# Schematic.net
KiCad netlist of a schematic drawn in EAGLE
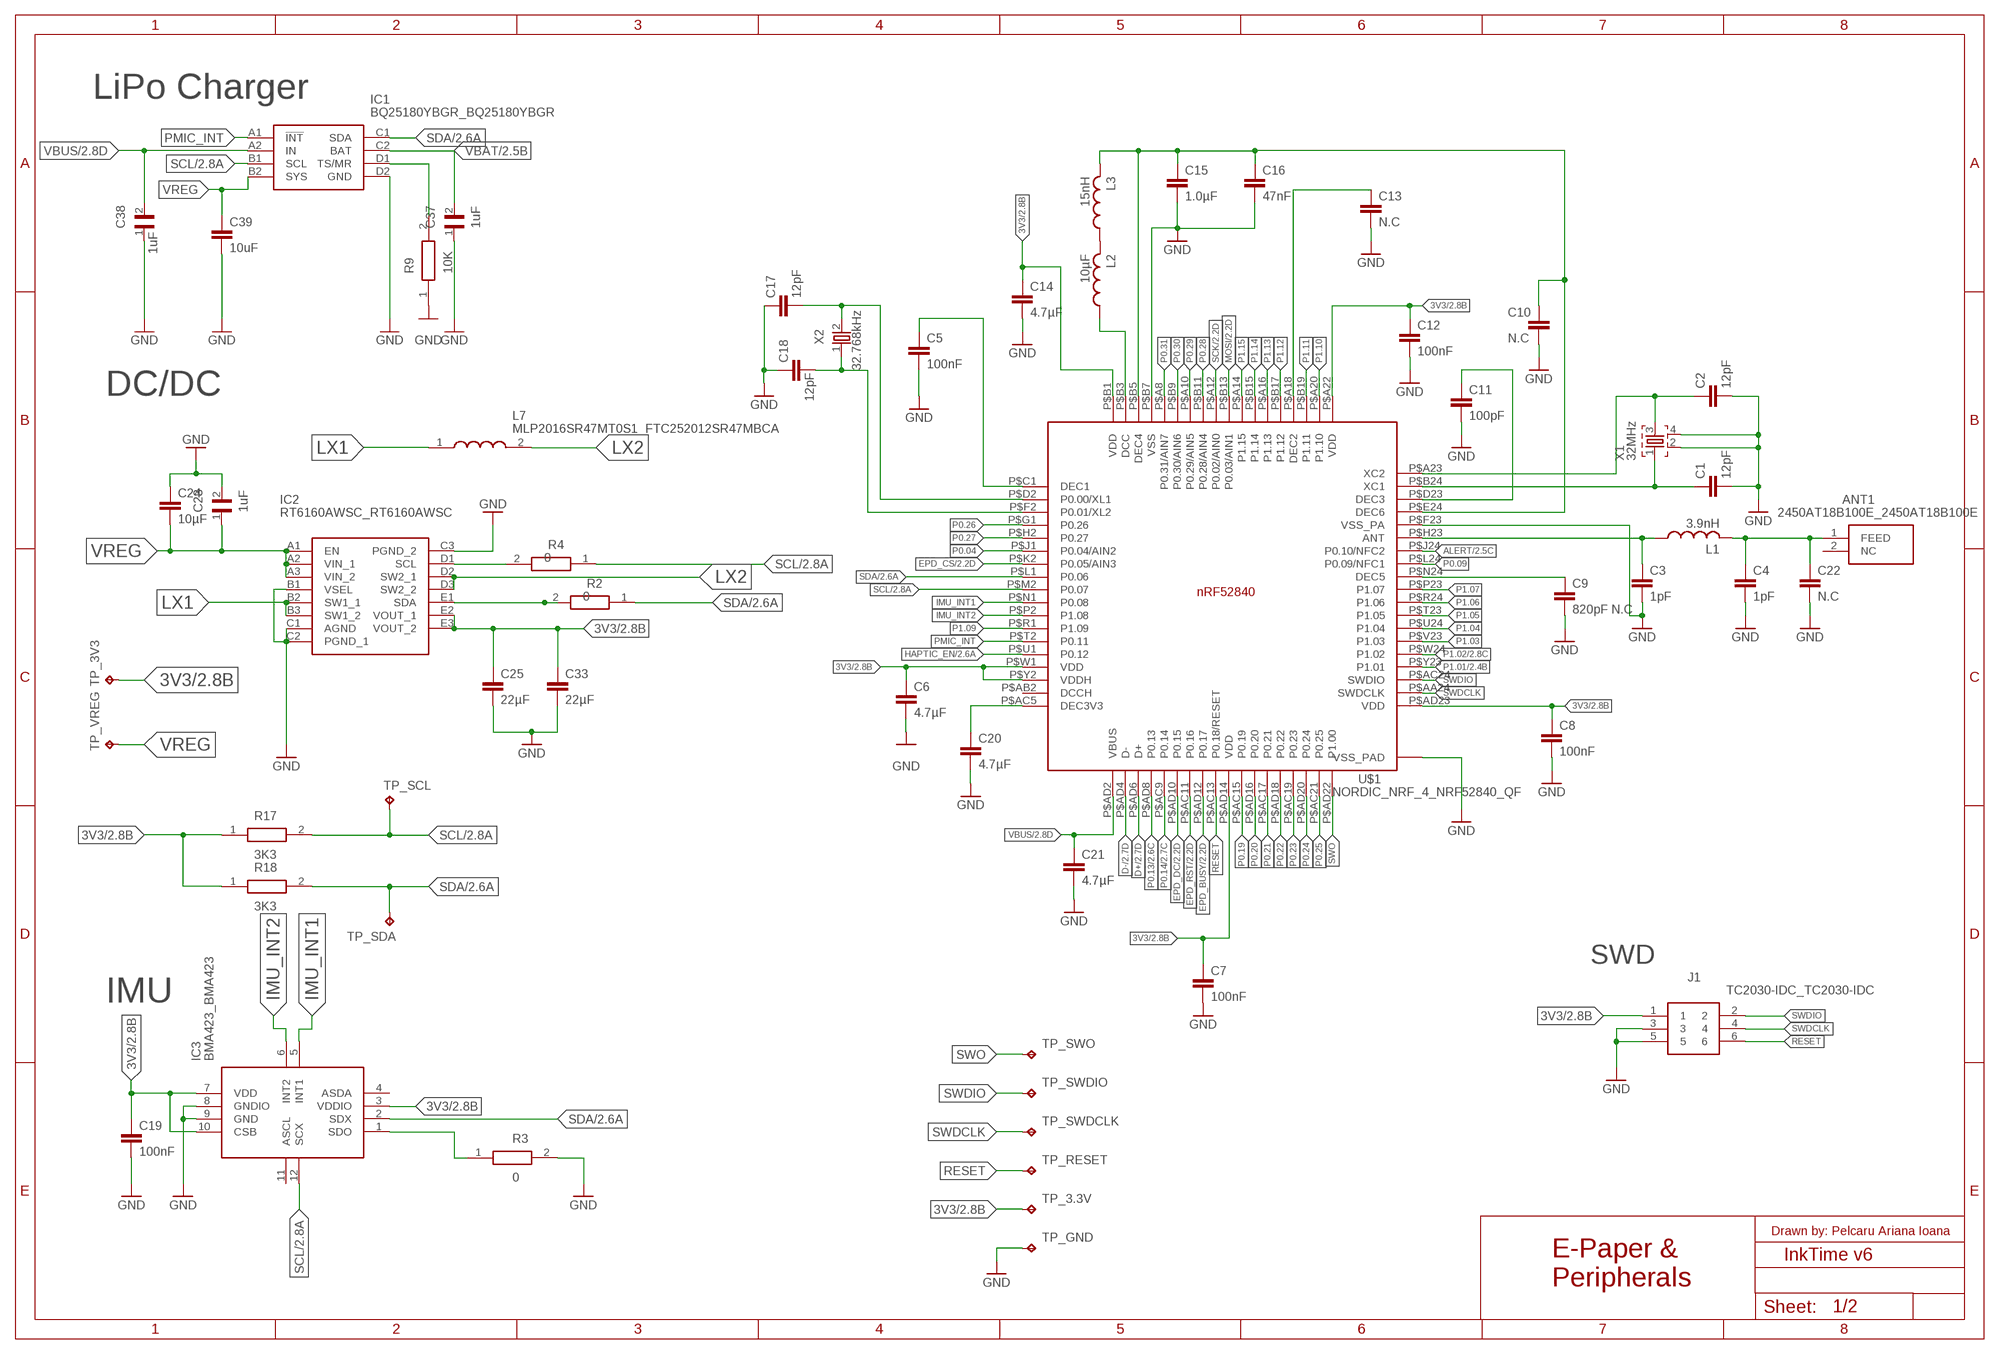
[diagram p0: schematic, sheet 1]
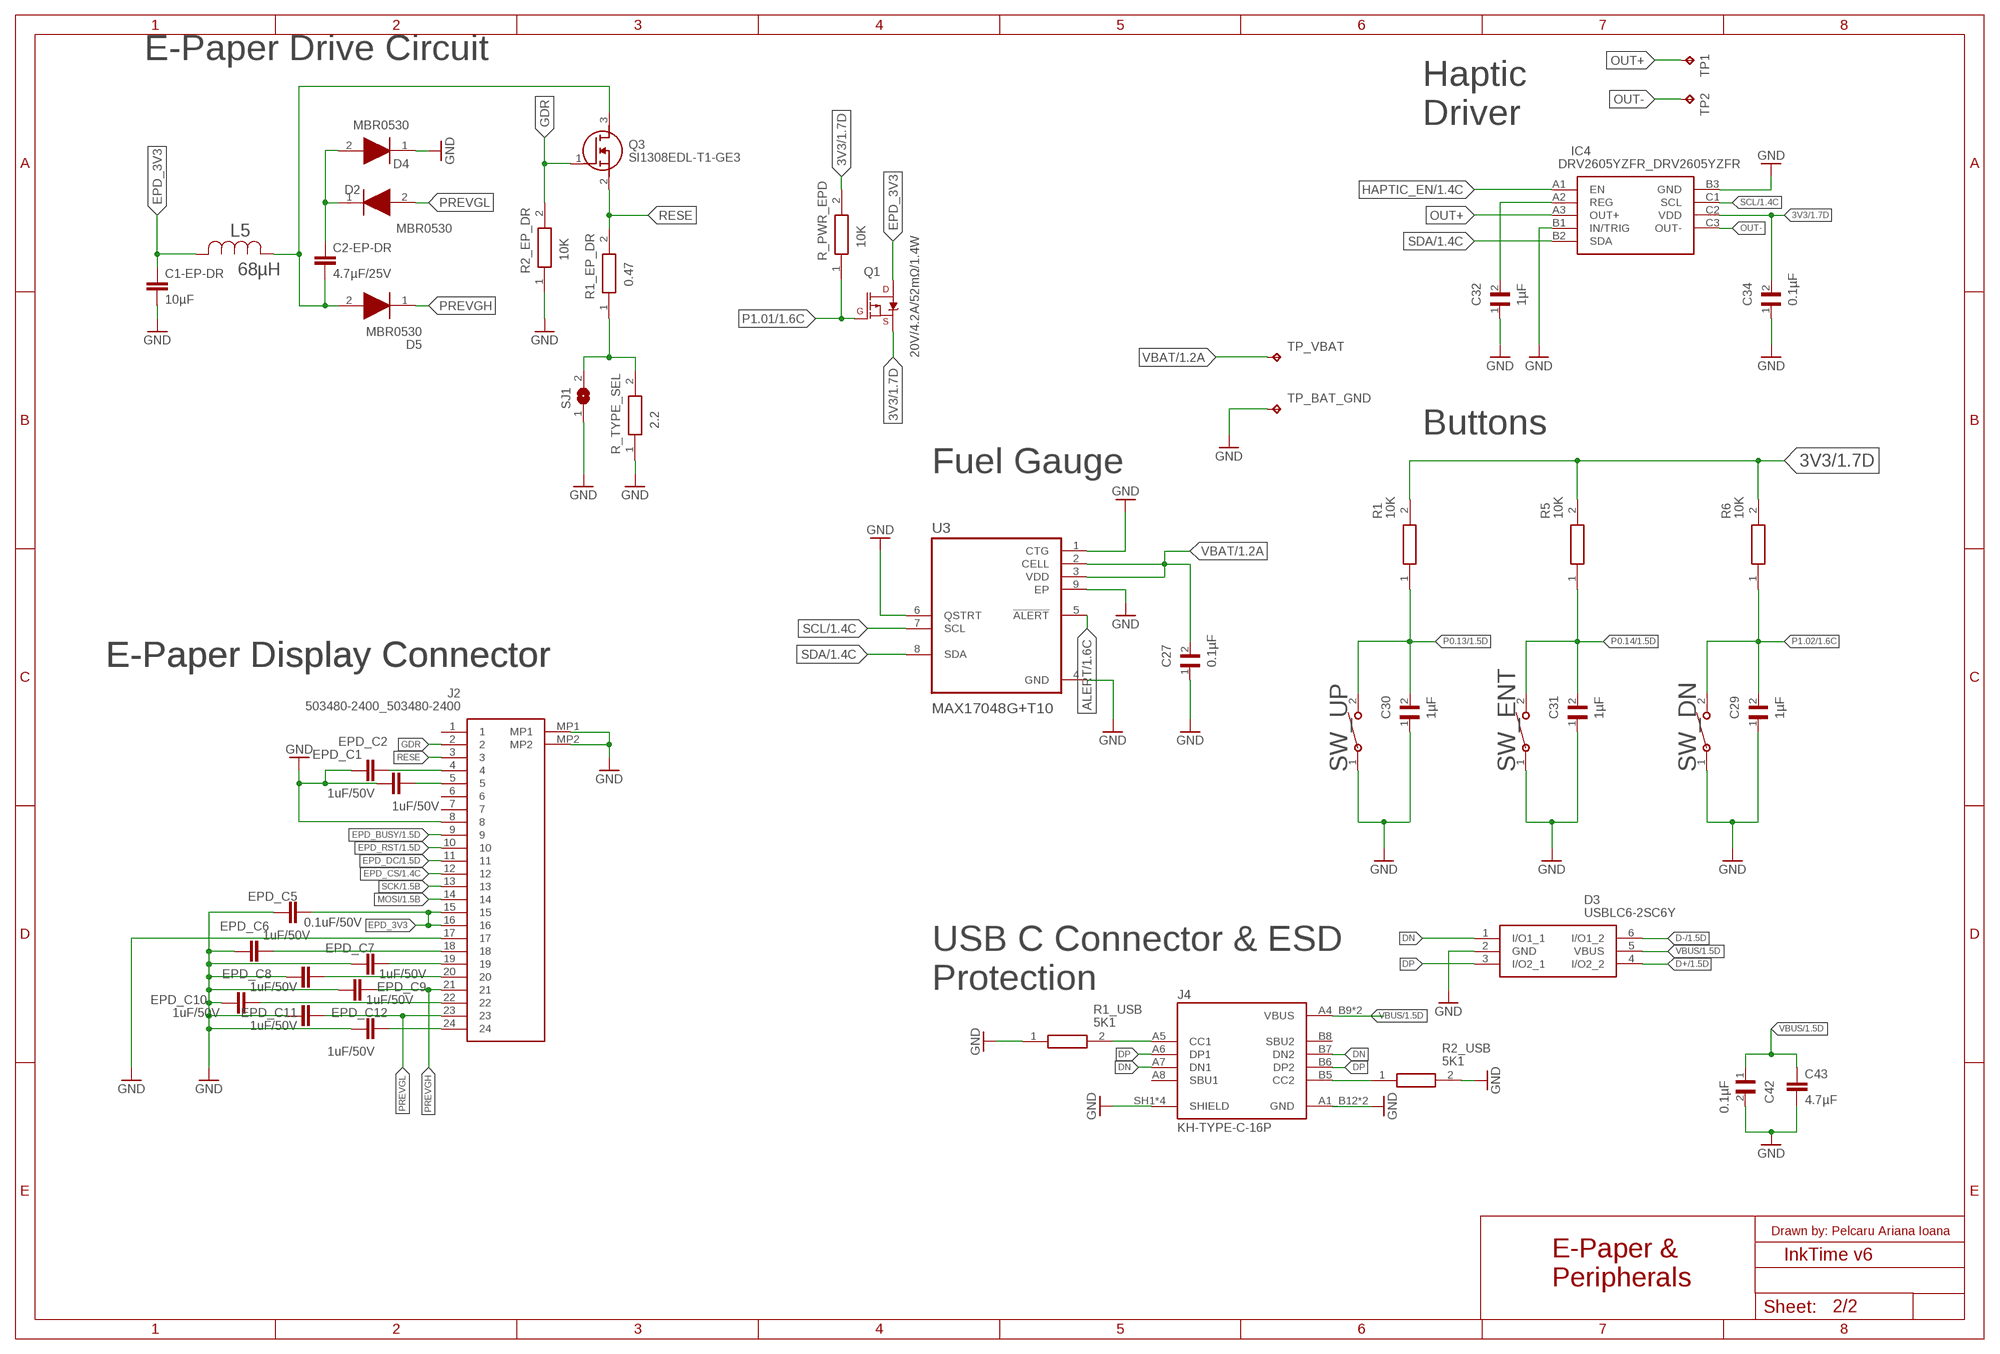
[diagram p1: schematic, sheet 2]

(export (version "E")
  (design (tool "Eeschema 10.0.6"))
  (components
    (comp (ref "C1-EP-DR")
      (value "10µF")
      (footprint "eagle-import:NORDIC_NRF_3_RESC0402_L")
      (libsource (lib "eagle-import") (part "InkTime_v5_vf.k0mpbVsCSkaTrqIbNtR9zw_NORDIC_NRF_3_CAPACITOR_0402_L"))
    )
    (comp (ref "C2-EP-DR")
      (value "4.7µF/25V")
      (footprint "eagle-import:NORDIC_NRF_3_RESC0603_L")
      (libsource (lib "eagle-import") (part "InkTime_v5_vf.k0mpbVsCSkaTrqIbNtR9zw_NORDIC_NRF_3_CAPACITOR_0603_L"))
    )
    (comp (ref "C27")
      (value "0.1µF")
      (footprint "eagle-import:GRM011R60J152KE01L_1_0201")
      (libsource (lib "eagle-import") (part "GRM011R60J152KE01L_1_GRM011R60J152KE01L"))
    )
    (comp (ref "C29")
      (value "1µF")
      (footprint "eagle-import:GRM011R60J152KE01L_1_0201")
      (libsource (lib "eagle-import") (part "GRM011R60J152KE01L_1_GRM011R60J152KE01L"))
    )
    (comp (ref "C30")
      (value "1µF")
      (footprint "eagle-import:GRM011R60J152KE01L_1_0201")
      (libsource (lib "eagle-import") (part "GRM011R60J152KE01L_1_GRM011R60J152KE01L"))
    )
    (comp (ref "C31")
      (value "1µF")
      (footprint "eagle-import:GRM011R60J152KE01L_1_0201")
      (libsource (lib "eagle-import") (part "GRM011R60J152KE01L_1_GRM011R60J152KE01L"))
    )
    (comp (ref "C32")
      (value "1µF")
      (footprint "eagle-import:GRM011R60J152KE01L_1_0201")
      (libsource (lib "eagle-import") (part "GRM011R60J152KE01L_1_GRM011R60J152KE01L"))
    )
    (comp (ref "C34")
      (value "0.1µF")
      (footprint "eagle-import:GRM011R60J152KE01L_2_CAPC0201X13N")
      (fields (field (name "MF") "Murata") (field (name "MP") "GRM011R60J152KE01L"))
      (libsource (lib "eagle-import") (part "InkTime_v5_vf.k0mpbVsCSkaTrqIbNtR9zw_GRM011R60J152KE01L_2_GRM011R60J152KE01L"))
    )
    (comp (ref "C42")
      (value "0.1µF")
      (footprint "eagle-import:GRM011R60J152KE01L_1_0201")
      (libsource (lib "eagle-import") (part "GRM011R60J152KE01L_1_GRM011R60J152KE01L"))
    )
    (comp (ref "C43")
      (value "4.7µF")
      (footprint "eagle-import:PERFECT_0402_0402")
      (libsource (lib "eagle-import") (part "InkTime_v5_vf.k0mpbVsCSkaTrqIbNtR9zw_PERFECT_0402_CAP_0402"))
    )
    (comp (ref "D2")
      (value "MBR0530")
      (footprint "eagle-import:ESP32_C6_LIBRARY_5_SOD3716X135N")
      (fields (field (name "MF") "ON Semiconductor"))
      (libsource (lib "eagle-import") (part "ESP32_C6_LIBRARY_5_MBR0530"))
    )
    (comp (ref "D3")
      (value "USBLC6-2SC6Y")
      (footprint "eagle-import:ESP32_C6_LIBRARY_3_SOT95P280X145-6N")
      (fields (field (name "MF") "STMicroelectronics"))
      (libsource (lib "eagle-import") (part "ESP32_C6_LIBRARY_3_USBLC6-2SC6Y"))
    )
    (comp (ref "D4")
      (value "MBR0530")
      (footprint "eagle-import:ESP32_C6_LIBRARY_5_SOD3716X135N")
      (fields (field (name "MF") "ON Semiconductor"))
      (libsource (lib "eagle-import") (part "ESP32_C6_LIBRARY_5_MBR0530"))
    )
    (comp (ref "D5")
      (value "MBR0530")
      (footprint "eagle-import:ESP32_C6_LIBRARY_5_SOD3716X135N")
      (fields (field (name "MF") "ON Semiconductor"))
      (libsource (lib "eagle-import") (part "ESP32_C6_LIBRARY_5_MBR0530"))
    )
    (comp (ref "EPD_C1")
      (value "1uF/50V")
      (footprint "eagle-import:PERFECT_0402_0402")
      (libsource (lib "eagle-import") (part "InkTime_v5_vf.k0mpbVsCSkaTrqIbNtR9zw_PERFECT_0402_CAP_0402"))
    )
    (comp (ref "EPD_C2")
      (value "1uF/50V")
      (footprint "eagle-import:PERFECT_0402_0402")
      (libsource (lib "eagle-import") (part "InkTime_v5_vf.k0mpbVsCSkaTrqIbNtR9zw_PERFECT_0402_CAP_0402"))
    )
    (comp (ref "EPD_C5")
      (value "0.1uF/50V")
      (footprint "eagle-import:NORDIC_NRF_3_RESC0201_L")
      (libsource (lib "eagle-import") (part "InkTime_v5_vf.k0mpbVsCSkaTrqIbNtR9zw_NORDIC_NRF_3_CAPACITOR_0201_L"))
    )
    (comp (ref "EPD_C6")
      (value "1uF/50V")
      (footprint "eagle-import:PERFECT_0402_0402")
      (libsource (lib "eagle-import") (part "InkTime_v5_vf.k0mpbVsCSkaTrqIbNtR9zw_PERFECT_0402_CAP_0402"))
    )
    (comp (ref "EPD_C7")
      (value "1uF/50V")
      (footprint "eagle-import:PERFECT_0402_0402")
      (libsource (lib "eagle-import") (part "InkTime_v5_vf.k0mpbVsCSkaTrqIbNtR9zw_PERFECT_0402_CAP_0402"))
    )
    (comp (ref "EPD_C8")
      (value "1uF/50V")
      (footprint "eagle-import:PERFECT_0402_0402")
      (libsource (lib "eagle-import") (part "InkTime_v5_vf.k0mpbVsCSkaTrqIbNtR9zw_PERFECT_0402_CAP_0402"))
    )
    (comp (ref "EPD_C9")
      (value "1uF/50V")
      (footprint "eagle-import:PERFECT_0402_0402")
      (libsource (lib "eagle-import") (part "InkTime_v5_vf.k0mpbVsCSkaTrqIbNtR9zw_PERFECT_0402_CAP_0402"))
    )
    (comp (ref "EPD_C10")
      (value "1uF/50V")
      (footprint "eagle-import:PERFECT_0402_0402")
      (libsource (lib "eagle-import") (part "InkTime_v5_vf.k0mpbVsCSkaTrqIbNtR9zw_PERFECT_0402_CAP_0402"))
    )
    (comp (ref "EPD_C11")
      (value "1uF/50V")
      (footprint "eagle-import:PERFECT_0402_0402")
      (libsource (lib "eagle-import") (part "InkTime_v5_vf.k0mpbVsCSkaTrqIbNtR9zw_PERFECT_0402_CAP_0402"))
    )
    (comp (ref "EPD_C12")
      (value "1uF/50V")
      (footprint "eagle-import:PERFECT_0402_0402")
      (libsource (lib "eagle-import") (part "InkTime_v5_vf.k0mpbVsCSkaTrqIbNtR9zw_PERFECT_0402_CAP_0402"))
    )
    (comp (ref "IC4")
      (value "DRV2605YZFR_DRV2605YZFR")
      (footprint "eagle-import:DRV2605YZFR_BGA9C50P3X3_144X144X62")
      (fields (field (name "ARROW_PART_NUMBER") "DRV2605YZFR"))
      (libsource (lib "eagle-import") (part "DRV2605YZFR_DRV2605YZFR"))
    )
    (comp (ref "J2")
      (value "503480-2400_503480-2400")
      (footprint "eagle-import:503480-2400_5034802400")
      (fields
        (field (name "MANUFACTURER_PART_NUMBER") "503480-2400")
        (field (name "MOUSER_PART_NUMBER") "538-503480-2400")
      )
      (libsource (lib "eagle-import") (part "503480-2400_503480-2400"))
    )
    (comp (ref "J4")
      (value "KH-TYPE-C-16P")
      (footprint "eagle-import:KH-TYPE-C-16P_KINGHELM_KH-TYPE-C-16P")
      (fields (field (name "MF") "kinghelm"))
      (libsource (lib "eagle-import") (part "KH-TYPE-C-16P_KH-TYPE-C-16P"))
    )
    (comp (ref "L5")
      (value "68µH")
      (footprint "eagle-import:ESP32_C6_LIBRARY_2_IND_4828-WE-TPC_WRE")
      (fields
        (field (name "MANUFACTURER_PART_NUMBER") "744043680")
        (field (name "COPYRIGHT") "Copyright (C) 2024 Ultra Librarian. All rights reserved.")
      )
      (libsource (lib "eagle-import") (part "ESP32_C6_LIBRARY_2_744043680IND_4828-WE-TPC_WRE"))
    )
    (comp (ref "Q1")
      (value "20V/4.2A/52mΩ/1.4W")
      (footprint "eagle-import:ESP32_C6_LIBRARY_4_ESP32_C6_LIBRARY_4_ESP32_C6_LIBRARY_4_ESP32_C6_LIBRARY_4_ESP32_WROVER_SPARKFUN-DISCRETESEMI_SOT23-3")
      (libsource (lib "eagle-import") (part "ESP32_C6_LIBRARY_4_ESP32_WROVER_SPARKFUN-DISCRETESEMI_MOSFET_PCH-DMG2305UX-7"))
    )
    (comp (ref "Q3")
      (value "SI1308EDL-T1-GE3")
      (footprint "eagle-import:ESP32_C6_LIBRARY_6_SOT65P210X110-3N")
      (fields (field (name "MF") "Vishay Siliconix"))
      (libsource (lib "eagle-import") (part "ESP32_C6_LIBRARY_6_SI1308EDL-T1-GE3"))
    )
    (comp (ref "R1")
      (value "10K")
      (footprint "eagle-import:CPF0201D7K68C1_0201")
      (libsource (lib "eagle-import") (part "InkTime_v5_vf.k0mpbVsCSkaTrqIbNtR9zw_CPF0201D7K68C1_CPF0201D7K68C1"))
    )
    (comp (ref "R1_EP_DR")
      (value "0.47")
      (footprint "eagle-import:CPF0201D7K68C1_0201")
      (libsource (lib "eagle-import") (part "InkTime_v5_vf.k0mpbVsCSkaTrqIbNtR9zw_CPF0201D7K68C1_CPF0201D7K68C1"))
    )
    (comp (ref "R1_USB")
      (value "5K1")
      (footprint "eagle-import:CPF0201D7K68C1_0201")
      (libsource (lib "eagle-import") (part "InkTime_v5_vf.k0mpbVsCSkaTrqIbNtR9zw_CPF0201D7K68C1_CPF0201D7K68C1"))
    )
    (comp (ref "R2_EP_DR")
      (value "10K")
      (footprint "eagle-import:CPF0201D7K68C1_0201")
      (libsource (lib "eagle-import") (part "InkTime_v5_vf.k0mpbVsCSkaTrqIbNtR9zw_CPF0201D7K68C1_CPF0201D7K68C1"))
    )
    (comp (ref "R2_USB")
      (value "5K1")
      (footprint "eagle-import:CPF0201D7K68C1_0201")
      (libsource (lib "eagle-import") (part "InkTime_v5_vf.k0mpbVsCSkaTrqIbNtR9zw_CPF0201D7K68C1_CPF0201D7K68C1"))
    )
    (comp (ref "R5")
      (value "10K")
      (footprint "eagle-import:CPF0201D7K68C1_0201")
      (libsource (lib "eagle-import") (part "InkTime_v5_vf.k0mpbVsCSkaTrqIbNtR9zw_CPF0201D7K68C1_CPF0201D7K68C1"))
    )
    (comp (ref "R6")
      (value "10K")
      (footprint "eagle-import:CPF0201D7K68C1_0201")
      (libsource (lib "eagle-import") (part "InkTime_v5_vf.k0mpbVsCSkaTrqIbNtR9zw_CPF0201D7K68C1_CPF0201D7K68C1"))
    )
    (comp (ref "R_PWR_EPD")
      (value "10K")
      (footprint "eagle-import:CPF0201D7K68C1_0201")
      (libsource (lib "eagle-import") (part "InkTime_v5_vf.k0mpbVsCSkaTrqIbNtR9zw_CPF0201D7K68C1_CPF0201D7K68C1"))
    )
    (comp (ref "R_TYPE_SEL")
      (value "2.2")
      (footprint "eagle-import:CPF0201D7K68C1_0201")
      (libsource (lib "eagle-import") (part "InkTime_v5_vf.k0mpbVsCSkaTrqIbNtR9zw_CPF0201D7K68C1_CPF0201D7K68C1"))
    )
    (comp (ref "SJ1")
      (value "ESP32_C6_LIBRARY_7_JUMPER_SJ")
      (footprint "eagle-import:ESP32_C6_LIBRARY_7_JUMPER_SJ")
      (libsource (lib "eagle-import") (part "ESP32_C6_LIBRARY_7_JUMPER_SJ"))
    )
    (comp (ref "SW_DN")
      (value "2025-10-22_07-23-44_LIBRARY_EVP-AKE31ASW_EVP-AKE31A_PAN")
      (footprint "eagle-import:2025-10-22_07-23-44_LIBRARY_SW_EVP-AKE31A_PAN")
      (fields
        (field (name "MANUFACTURER_PART_NUMBER") "EVP-AKE31A")
        (field (name "COPYRIGHT") "Copyright (C) 2025 Ultra Librarian. All rights reserved.")
      )
      (libsource (lib "eagle-import") (part "2025-10-22_07-23-44_LIBRARY_EVP-AKE31ASW_EVP-AKE31A_PAN"))
    )
    (comp (ref "SW_ENT")
      (value "2025-10-22_07-23-44_LIBRARY_EVP-AKE31ASW_EVP-AKE31A_PAN")
      (footprint "eagle-import:2025-10-22_07-23-44_LIBRARY_SW_EVP-AKE31A_PAN")
      (fields
        (field (name "MANUFACTURER_PART_NUMBER") "EVP-AKE31A")
        (field (name "COPYRIGHT") "Copyright (C) 2025 Ultra Librarian. All rights reserved.")
      )
      (libsource (lib "eagle-import") (part "2025-10-22_07-23-44_LIBRARY_EVP-AKE31ASW_EVP-AKE31A_PAN"))
    )
    (comp (ref "SW_UP")
      (value "2025-10-22_07-23-44_LIBRARY_EVP-AKE31ASW_EVP-AKE31A_PAN")
      (footprint "eagle-import:2025-10-22_07-23-44_LIBRARY_SW_EVP-AKE31A_PAN")
      (fields
        (field (name "MANUFACTURER_PART_NUMBER") "EVP-AKE31A")
        (field (name "COPYRIGHT") "Copyright (C) 2025 Ultra Librarian. All rights reserved.")
      )
      (libsource (lib "eagle-import") (part "2025-10-22_07-23-44_LIBRARY_EVP-AKE31ASW_EVP-AKE31A_PAN"))
    )
    (comp (ref "TP1")
      (value "HECTOR_WATCH_1_TPTP20R")
      (footprint "eagle-import:HECTOR_WATCH_1_TP20R")
      (libsource (lib "eagle-import") (part "InkTime_v5_vf.k0mpbVsCSkaTrqIbNtR9zw_HECTOR_WATCH_1_TPTP20R"))
    )
    (comp (ref "TP2")
      (value "HECTOR_WATCH_1_TPTP20R")
      (footprint "eagle-import:HECTOR_WATCH_1_TP20R")
      (libsource (lib "eagle-import") (part "InkTime_v5_vf.k0mpbVsCSkaTrqIbNtR9zw_HECTOR_WATCH_1_TPTP20R"))
    )
    (comp (ref "TP_BAT_GND")
      (value "HECTOR_WATCH_1_TPTP20R")
      (footprint "eagle-import:HECTOR_WATCH_1_TP20R")
      (libsource (lib "eagle-import") (part "InkTime_v5_vf.k0mpbVsCSkaTrqIbNtR9zw_HECTOR_WATCH_1_TPTP20R"))
    )
    (comp (ref "TP_VBAT")
      (value "HECTOR_WATCH_1_TPTP20R")
      (footprint "eagle-import:HECTOR_WATCH_1_TP20R")
      (libsource (lib "eagle-import") (part "InkTime_v5_vf.k0mpbVsCSkaTrqIbNtR9zw_HECTOR_WATCH_1_TPTP20R"))
    )
    (comp (ref "U3")
      (value "MAX17048G+T10")
      (footprint "eagle-import:ESP32_C6_LIBRARY_SON50P200X200X80-9N")
      (fields (field (name "MF") "Analog Devices"))
      (libsource (lib "eagle-import") (part "ESP32_C6_LIBRARY_MAX17048G+T10"))
    )
    (comp (ref "ANT1")
      (value "2450AT18B100E_2450AT18B100E")
      (footprint "eagle-import:2450AT18B100E_ANTC3216X140N")
      (fields
        (field (name "ARROW_PART_NUMBER") "2450AT18B100E")
        (field (name "MOUSER_PART_NUMBER") "609-2450AT18B100E")
      )
      (libsource (lib "eagle-import") (part "2450AT18B100E_2450AT18B100E"))
    )
    (comp (ref "C1")
      (value "12pF")
      (footprint "eagle-import:NORDIC_NRF_3_RESC0201_L")
      (libsource (lib "eagle-import") (part "InkTime_v5_vf.k0mpbVsCSkaTrqIbNtR9zw_NORDIC_NRF_3_CAPACITOR_0201_L"))
    )
    (comp (ref "C2")
      (value "12pF")
      (footprint "eagle-import:NORDIC_NRF_3_RESC0201_L")
      (libsource (lib "eagle-import") (part "InkTime_v5_vf.k0mpbVsCSkaTrqIbNtR9zw_NORDIC_NRF_3_CAPACITOR_0201_L"))
    )
    (comp (ref "C3")
      (value "1pF")
      (footprint "eagle-import:NORDIC_NRF_3_RESC0201_L")
      (libsource (lib "eagle-import") (part "InkTime_v5_vf.k0mpbVsCSkaTrqIbNtR9zw_NORDIC_NRF_3_CAPACITOR_0201_L"))
    )
    (comp (ref "C4")
      (value "1pF")
      (footprint "eagle-import:NORDIC_NRF_3_RESC0201_L")
      (libsource (lib "eagle-import") (part "InkTime_v5_vf.k0mpbVsCSkaTrqIbNtR9zw_NORDIC_NRF_3_CAPACITOR_0201_L"))
    )
    (comp (ref "C5")
      (value "100nF")
      (footprint "eagle-import:NORDIC_NRF_3_RESC0201_L")
      (libsource (lib "eagle-import") (part "InkTime_v5_vf.k0mpbVsCSkaTrqIbNtR9zw_NORDIC_NRF_3_CAPACITOR_0201_L"))
    )
    (comp (ref "C6")
      (value "4.7µF")
      (footprint "eagle-import:PERFECT_0402_0402")
      (libsource (lib "eagle-import") (part "InkTime_v5_vf.k0mpbVsCSkaTrqIbNtR9zw_PERFECT_0402_CAP_0402"))
    )
    (comp (ref "C7")
      (value "100nF")
      (footprint "eagle-import:NORDIC_NRF_3_RESC0201_L")
      (libsource (lib "eagle-import") (part "InkTime_v5_vf.k0mpbVsCSkaTrqIbNtR9zw_NORDIC_NRF_3_CAPACITOR_0201_L"))
    )
    (comp (ref "C8")
      (value "100nF")
      (footprint "eagle-import:NORDIC_NRF_3_RESC0201_L")
      (libsource (lib "eagle-import") (part "InkTime_v5_vf.k0mpbVsCSkaTrqIbNtR9zw_NORDIC_NRF_3_CAPACITOR_0201_L"))
    )
    (comp (ref "C9")
      (value "820pF N.C")
      (footprint "eagle-import:NORDIC_NRF_3_RESC0201_L")
      (libsource (lib "eagle-import") (part "NORDIC_NRF_3_CAPACITOR_0201_L"))
    )
    (comp (ref "C10")
      (value "N.C")
      (footprint "eagle-import:PERFECT_0402_0402")
      (libsource (lib "eagle-import") (part "InkTime_v5_vf.k0mpbVsCSkaTrqIbNtR9zw_PERFECT_0402_CAP_0402"))
    )
    (comp (ref "C11")
      (value "100pF")
      (footprint "eagle-import:NORDIC_NRF_3_RESC0201_L")
      (libsource (lib "eagle-import") (part "InkTime_v5_vf.k0mpbVsCSkaTrqIbNtR9zw_NORDIC_NRF_3_CAPACITOR_0201_L"))
    )
    (comp (ref "C12")
      (value "100nF")
      (footprint "eagle-import:NORDIC_NRF_3_RESC0201_L")
      (libsource (lib "eagle-import") (part "InkTime_v5_vf.k0mpbVsCSkaTrqIbNtR9zw_NORDIC_NRF_3_CAPACITOR_0201_L"))
    )
    (comp (ref "C13")
      (value "N.C")
      (footprint "eagle-import:NORDIC_NRF_3_RESC0201_L")
      (libsource (lib "eagle-import") (part "NORDIC_NRF_3_CAPACITOR_0201_L"))
    )
    (comp (ref "C14")
      (value "4.7µF")
      (footprint "eagle-import:PERFECT_0402_0402")
      (libsource (lib "eagle-import") (part "InkTime_v5_vf.k0mpbVsCSkaTrqIbNtR9zw_PERFECT_0402_CAP_0402"))
    )
    (comp (ref "C15")
      (value "1.0µF")
      (footprint "eagle-import:PERFECT_0402_0402")
      (libsource (lib "eagle-import") (part "InkTime_v5_vf.k0mpbVsCSkaTrqIbNtR9zw_PERFECT_0402_CAP_0402"))
    )
    (comp (ref "C16")
      (value "47nF")
      (footprint "eagle-import:NORDIC_NRF_3_RESC0201_L")
      (libsource (lib "eagle-import") (part "InkTime_v5_vf.k0mpbVsCSkaTrqIbNtR9zw_NORDIC_NRF_3_CAPACITOR_0201_L"))
    )
    (comp (ref "C17")
      (value "12pF")
      (footprint "eagle-import:NORDIC_NRF_3_RESC0201_L")
      (libsource (lib "eagle-import") (part "InkTime_v5_vf.k0mpbVsCSkaTrqIbNtR9zw_NORDIC_NRF_3_CAPACITOR_0201_L"))
    )
    (comp (ref "C18")
      (value "12pF")
      (footprint "eagle-import:NORDIC_NRF_3_RESC0201_L")
      (libsource (lib "eagle-import") (part "InkTime_v5_vf.k0mpbVsCSkaTrqIbNtR9zw_NORDIC_NRF_3_CAPACITOR_0201_L"))
    )
    (comp (ref "C19")
      (value "100nF")
      (footprint "eagle-import:NORDIC_NRF_3_RESC0201_L")
      (libsource (lib "eagle-import") (part "InkTime_v5_vf.k0mpbVsCSkaTrqIbNtR9zw_NORDIC_NRF_3_CAPACITOR_0201_L"))
    )
    (comp (ref "C20")
      (value "4.7µF")
      (footprint "eagle-import:PERFECT_0402_0402")
      (libsource (lib "eagle-import") (part "InkTime_v5_vf.k0mpbVsCSkaTrqIbNtR9zw_PERFECT_0402_CAP_0402"))
    )
    (comp (ref "C21")
      (value "4.7µF")
      (footprint "eagle-import:PERFECT_0402_0402")
      (libsource (lib "eagle-import") (part "InkTime_v5_vf.k0mpbVsCSkaTrqIbNtR9zw_PERFECT_0402_CAP_0402"))
    )
    (comp (ref "C22")
      (value "N.C")
      (footprint "eagle-import:NORDIC_NRF_3_RESC0201_L")
      (libsource (lib "eagle-import") (part "NORDIC_NRF_3_CAPACITOR_0201_L"))
    )
    (comp (ref "C23")
      (value "1uF")
      (footprint "eagle-import:GRM011R60J152KE01L_2_CAPC0201X13N")
      (fields (field (name "MF") "Murata") (field (name "MP") "GRM011R60J152KE01L"))
      (libsource (lib "eagle-import") (part "GRM011R60J152KE01L_2_GRM011R60J152KE01L"))
    )
    (comp (ref "C24")
      (value "10µF")
      (footprint "eagle-import:PERFECT_0402_0402")
      (libsource (lib "eagle-import") (part "InkTime_v5_vf.k0mpbVsCSkaTrqIbNtR9zw_PERFECT_0402_CAP_0402"))
    )
    (comp (ref "C25")
      (value "22µF")
      (footprint "eagle-import:PERFECT_0402_0402")
      (libsource (lib "eagle-import") (part "InkTime_v5_vf.k0mpbVsCSkaTrqIbNtR9zw_PERFECT_0402_CAP_0402"))
    )
    (comp (ref "C33")
      (value "22µF")
      (footprint "eagle-import:PERFECT_0402_0402")
      (libsource (lib "eagle-import") (part "InkTime_v5_vf.k0mpbVsCSkaTrqIbNtR9zw_PERFECT_0402_CAP_0402"))
    )
    (comp (ref "C37")
      (value "1uF")
      (footprint "eagle-import:GRM011R60J152KE01L_2_CAPC0201X13N")
      (fields (field (name "MF") "Murata") (field (name "MP") "GRM011R60J152KE01L"))
      (libsource (lib "eagle-import") (part "GRM011R60J152KE01L_2_GRM011R60J152KE01L"))
    )
    (comp (ref "C38")
      (value "1uF")
      (footprint "eagle-import:GRM011R60J152KE01L_2_CAPC0201X13N")
      (fields (field (name "MF") "Murata") (field (name "MP") "GRM011R60J152KE01L"))
      (libsource (lib "eagle-import") (part "GRM011R60J152KE01L_2_GRM011R60J152KE01L"))
    )
    (comp (ref "C39")
      (value "10uF")
      (footprint "eagle-import:PERFECT_0402_0402")
      (libsource (lib "eagle-import") (part "PERFECT_0402_CAP_0402"))
    )
    (comp (ref "IC1")
      (value "BQ25180YBGR_BQ25180YBGR")
      (footprint "eagle-import:BQ25180YBGR_BGA8C40P2X4_100X155X50")
      (fields
        (field (name "ARROW_PART_NUMBER") "BQ25180YBGR")
        (field (name "MOUSER_PART_NUMBER") "595-BQ25180YBGR")
      )
      (libsource (lib "eagle-import") (part "BQ25180YBGR_BQ25180YBGR"))
    )
    (comp (ref "IC2")
      (value "RT6160AWSC_RT6160AWSC")
      (footprint "eagle-import:RT6160AWSC_BGA15C40P3X5_140X230X60")
      (fields
        (field (name "MANUFACTURER_PART_NUMBER") "RT6160AWSC")
        (field (name "MOUSER_PART_NUMBER") "835-RT6160AWSC")
      )
      (libsource (lib "eagle-import") (part "RT6160AWSC_RT6160AWSC"))
    )
    (comp (ref "IC3")
      (value "BMA423_BMA423")
      (footprint "eagle-import:BMA423_BMA423")
      (fields (field (name "ARROW_PART_NUMBER") "BMA423") (field (name "MOUSER_PART_NUMBER") "262-BMA423"))
      (libsource (lib "eagle-import") (part "BMA423_BMA423"))
    )
    (comp (ref "J1")
      (value "TC2030-IDC_TC2030-IDC")
      (footprint "eagle-import:TC2030-IDC_TC2030IDC")
      (fields (field (name "MANUFACTURER_PART_NUMBER") "TC2030-IDC"))
      (libsource (lib "eagle-import") (part "TC2030-IDC_TC2030-IDC"))
    )
    (comp (ref "L1")
      (value "3.9nH")
      (footprint "eagle-import:NORDIC_NRF_2_RESC0402_L")
      (libsource (lib "eagle-import") (part "NORDIC_NRF_2_INDUCTOR_0402_L"))
    )
    (comp (ref "L2")
      (value "10µF")
      (footprint "eagle-import:NORDIC_NRF_2_RESC0402_L")
      (libsource (lib "eagle-import") (part "NORDIC_NRF_2_INDUCTOR_0402_L"))
    )
    (comp (ref "L3")
      (value "15nH")
      (footprint "eagle-import:NORDIC_NRF_2_RESC0402_L")
      (libsource (lib "eagle-import") (part "NORDIC_NRF_2_INDUCTOR_0402_L"))
    )
    (comp (ref "L7")
      (value "MLP2016SR47MT0S1_FTC252012SR47MBCA")
      (footprint "eagle-import:MLP2016SR47MT0S1_INDC2016X100N")
      (fields (field (name "MANUFACTURER_PART_NUMBER") "FTC252012SR47MBCA"))
      (libsource (lib "eagle-import") (part "MLP2016SR47MT0S1_FTC252012SR47MBCA"))
    )
    (comp (ref "R2")
      (value "0")
      (footprint "eagle-import:CPF0201D7K68C1_0201")
      (libsource (lib "eagle-import") (part "CPF0201D7K68C1_CPF0201D7K68C1"))
    )
    (comp (ref "R3")
      (value "0")
      (footprint "eagle-import:CPF0201D7K68C1_0201")
      (libsource (lib "eagle-import") (part "CPF0201D7K68C1_CPF0201D7K68C1"))
    )
    (comp (ref "R4")
      (value "0")
      (footprint "eagle-import:CPF0201D7K68C1_0201")
      (libsource (lib "eagle-import") (part "CPF0201D7K68C1_CPF0201D7K68C1"))
    )
    (comp (ref "R9")
      (value "10K")
      (footprint "eagle-import:CPF0201D7K68C1_0201")
      (libsource (lib "eagle-import") (part "InkTime_v5_vf.k0mpbVsCSkaTrqIbNtR9zw_CPF0201D7K68C1_CPF0201D7K68C1"))
    )
    (comp (ref "R17")
      (value "3K3")
      (footprint "eagle-import:ERA-1AEB3401C_0201")
      (libsource (lib "eagle-import") (part "ERA-1AEB3401C_CPF0201D7K68C1"))
    )
    (comp (ref "R18")
      (value "3K3")
      (footprint "eagle-import:ERA-1AEB3401C_0201")
      (libsource (lib "eagle-import") (part "ERA-1AEB3401C_CPF0201D7K68C1"))
    )
    (comp (ref "TP_3.3V")
      (value "HECTOR_WATCH_1_TPTP20R")
      (footprint "eagle-import:HECTOR_WATCH_1_TP20R")
      (libsource (lib "eagle-import") (part "InkTime_v5_vf.k0mpbVsCSkaTrqIbNtR9zw_HECTOR_WATCH_1_TPTP20R"))
    )
    (comp (ref "TP_3V3")
      (value "HECTOR_WATCH_1_TPTP20R")
      (footprint "eagle-import:HECTOR_WATCH_1_TP20R")
      (libsource (lib "eagle-import") (part "HECTOR_WATCH_1_TPTP20R"))
    )
    (comp (ref "TP_GND")
      (value "HECTOR_WATCH_1_TPTP20R")
      (footprint "eagle-import:HECTOR_WATCH_1_TP20R")
      (libsource (lib "eagle-import") (part "InkTime_v5_vf.k0mpbVsCSkaTrqIbNtR9zw_HECTOR_WATCH_1_TPTP20R"))
    )
    (comp (ref "TP_RESET")
      (value "HECTOR_WATCH_1_TPTP20R")
      (footprint "eagle-import:HECTOR_WATCH_1_TP20R")
      (libsource (lib "eagle-import") (part "InkTime_v5_vf.k0mpbVsCSkaTrqIbNtR9zw_HECTOR_WATCH_1_TPTP20R"))
    )
    (comp (ref "TP_SCL")
      (value "HECTOR_WATCH_1_TPTP20R")
      (footprint "eagle-import:HECTOR_WATCH_1_TP20R")
      (libsource (lib "eagle-import") (part "HECTOR_WATCH_1_TPTP20R"))
    )
    (comp (ref "TP_SDA")
      (value "HECTOR_WATCH_1_TPTP20R")
      (footprint "eagle-import:HECTOR_WATCH_1_TP20R")
      (libsource (lib "eagle-import") (part "HECTOR_WATCH_1_TPTP20R"))
    )
    (comp (ref "TP_SWDCLK")
      (value "HECTOR_WATCH_1_TPTP20R")
      (footprint "eagle-import:HECTOR_WATCH_1_TP20R")
      (libsource (lib "eagle-import") (part "InkTime_v5_vf.k0mpbVsCSkaTrqIbNtR9zw_HECTOR_WATCH_1_TPTP20R"))
    )
    (comp (ref "TP_SWDIO")
      (value "HECTOR_WATCH_1_TPTP20R")
      (footprint "eagle-import:HECTOR_WATCH_1_TP20R")
      (libsource (lib "eagle-import") (part "InkTime_v5_vf.k0mpbVsCSkaTrqIbNtR9zw_HECTOR_WATCH_1_TPTP20R"))
    )
    (comp (ref "TP_SWO")
      (value "HECTOR_WATCH_1_TPTP20R")
      (footprint "eagle-import:HECTOR_WATCH_1_TP20R")
      (libsource (lib "eagle-import") (part "InkTime_v5_vf.k0mpbVsCSkaTrqIbNtR9zw_HECTOR_WATCH_1_TPTP20R"))
    )
    (comp (ref "TP_VREG")
      (value "HECTOR_WATCH_1_TPTP20R")
      (footprint "eagle-import:HECTOR_WATCH_1_TP20R")
      (libsource (lib "eagle-import") (part "HECTOR_WATCH_1_TPTP20R"))
    )
    (comp (ref "U$1")
      (value "NORDIC_NRF_4_NRF52840_QF")
      (footprint "eagle-import:NORDIC_NRF_4_AQFN50P700X700X85_HS-74N")
      (libsource (lib "eagle-import") (part "NORDIC_NRF_4_NRF52840_QF"))
    )
    (comp (ref "X1")
      (value "32MHz")
      (footprint "eagle-import:NORDIC_NRF_BT-XTAL_2016_N")
      (libsource (lib "eagle-import") (part "NORDIC_NRF_XTAL_32MHZ"))
    )
    (comp (ref "X2")
      (value "32.768kHz")
      (footprint "eagle-import:NORDIC_NRF_1_XTAL_3215_N")
      (libsource (lib "eagle-import") (part "NORDIC_NRF_1_XTAL_32KHZ"))
    )
  )
  (nets
    (net (code "1") (name "3V3") (class "Default")
      (node (ref "C12") (pin "1") (pinfunction "1_1") (pintype "passive"))
      (node (ref "C14") (pin "1") (pinfunction "1_1") (pintype "passive"))
      (node (ref "C19") (pin "1") (pinfunction "1_1") (pintype "passive"))
      (node (ref "C25") (pin "1") (pinfunction "1_1") (pintype "passive"))
      (node (ref "C33") (pin "1") (pinfunction "1_1") (pintype "passive"))
      (node (ref "C6") (pin "1") (pinfunction "1_1") (pintype "passive"))
      (node (ref "C7") (pin "1") (pinfunction "1_1") (pintype "passive"))
      (node (ref "C8") (pin "1") (pinfunction "1_1") (pintype "passive"))
      (node (ref "IC2") (pin "E2") (pinfunction "VOUT_1_E2") (pintype "bidirectional"))
      (node (ref "IC2") (pin "E3") (pinfunction "VOUT_2_E3") (pintype "bidirectional"))
      (node (ref "IC3") (pin "10") (pinfunction "CSB_10") (pintype "bidirectional"))
      (node (ref "IC3") (pin "3") (pinfunction "VDDIO_3") (pintype "bidirectional"))
      (node (ref "IC3") (pin "7") (pinfunction "VDD_7") (pintype "bidirectional"))
      (node (ref "J1") (pin "1") (pinfunction "1_1") (pintype "bidirectional"))
      (node (ref "Q1") (pin "2") (pinfunction "S_2") (pintype "bidirectional"))
      (node (ref "R1") (pin "2") (pinfunction "2_2") (pintype "bidirectional"))
      (node (ref "R17") (pin "1") (pinfunction "1_1") (pintype "bidirectional"))
      (node (ref "R18") (pin "1") (pinfunction "1_1") (pintype "bidirectional"))
      (node (ref "R5") (pin "2") (pinfunction "2_2") (pintype "bidirectional"))
      (node (ref "R6") (pin "2") (pinfunction "2_2") (pintype "bidirectional"))
      (node (ref "R_PWR_EPD") (pin "2") (pinfunction "2_2") (pintype "bidirectional"))
      (node (ref "TP_3.3V") (pin "TP") (pinfunction "TP_TP") (pintype "input"))
      (node (ref "TP_3V3") (pin "TP") (pinfunction "TP_TP") (pintype "input"))
      (node (ref "U$1") (pin "P$A22") (pinfunction "VDD_P$A22") (pintype "power_in"))
      (node (ref "U$1") (pin "P$AD14") (pinfunction "VDD_P$AD14") (pintype "power_in"))
      (node (ref "U$1") (pin "P$AD23") (pinfunction "VDD_P$AD23") (pintype "power_in"))
      (node (ref "U$1") (pin "P$B1") (pinfunction "VDD_P$B1") (pintype "power_in"))
      (node (ref "U$1") (pin "P$W1") (pinfunction "VDD_P$W1") (pintype "power_in"))
      (node (ref "U$1") (pin "P$Y2") (pinfunction "VDDH_P$Y2") (pintype "power_in"))
    )
    (net (code "2") (name "3V3{slash}1.7D") (class "Default")
      (node (ref "C34") (pin "2") (pinfunction "2_2") (pintype "passive"))
      (node (ref "IC4") (pin "C2") (pinfunction "VDD_C2") (pintype "bidirectional"))
    )
    (net (code "3") (name "ALERT") (class "Default")
      (node (ref "U$1") (pin "P$J24") (pinfunction "P0.10/NFC2_P$J24") (pintype "bidirectional"))
      (node (ref "U3") (pin "5") (pinfunction "~{ALERT}_5") (pintype "output"))
    )
    (net (code "4") (name "D+") (class "Default")
      (node (ref "D3") (pin "4") (pinfunction "I/O2_2_4") (pintype "bidirectional"))
      (node (ref "U$1") (pin "P$AD6") (pinfunction "D+_P$AD6") (pintype "bidirectional"))
    )
    (net (code "5") (name "D-") (class "Default")
      (node (ref "D3") (pin "6") (pinfunction "I/O1_2_6") (pintype "bidirectional"))
      (node (ref "U$1") (pin "P$AD4") (pinfunction "D-_P$AD4") (pintype "bidirectional"))
    )
    (net (code "6") (name "DN") (class "Default")
      (node (ref "D3") (pin "1") (pinfunction "I/O1_1_1") (pintype "bidirectional"))
      (node (ref "J4") (pin "A7") (pinfunction "DN1_A7") (pintype "bidirectional"))
      (node (ref "J4") (pin "B7") (pinfunction "DN2_B7") (pintype "bidirectional"))
    )
    (net (code "7") (name "DP") (class "Default")
      (node (ref "D3") (pin "3") (pinfunction "I/O2_1_3") (pintype "bidirectional"))
      (node (ref "J4") (pin "A6") (pinfunction "DP1_A6") (pintype "bidirectional"))
      (node (ref "J4") (pin "B6") (pinfunction "DP2_B6") (pintype "bidirectional"))
    )
    (net (code "8") (name "EPD_3V3") (class "Default")
      (node (ref "C1-EP-DR") (pin "1") (pinfunction "1_1") (pintype "passive"))
      (node (ref "EPD_C5") (pin "2") (pinfunction "2_2") (pintype "passive"))
      (node (ref "J2") (pin "15") (pinfunction "15_15") (pintype "bidirectional"))
      (node (ref "J2") (pin "16") (pinfunction "16_16") (pintype "bidirectional"))
      (node (ref "L5") (pin "2") (pinfunction "2_2") (pintype "passive"))
      (node (ref "Q1") (pin "3") (pinfunction "D_3") (pintype "bidirectional"))
    )
    (net (code "9") (name "EPD_BUSY") (class "Default")
      (node (ref "J2") (pin "9") (pinfunction "9_9") (pintype "bidirectional"))
      (node (ref "U$1") (pin "P$AD12") (pinfunction "P0.17_P$AD12") (pintype "bidirectional"))
    )
    (net (code "10") (name "EPD_CS") (class "Default")
      (node (ref "J2") (pin "12") (pinfunction "12_12") (pintype "bidirectional"))
      (node (ref "U$1") (pin "P$K2") (pinfunction "P0.05/AIN3_P$K2") (pintype "bidirectional"))
    )
    (net (code "11") (name "EPD_DC") (class "Default")
      (node (ref "J2") (pin "11") (pinfunction "11_11") (pintype "bidirectional"))
      (node (ref "U$1") (pin "P$AD10") (pinfunction "P0.15_P$AD10") (pintype "bidirectional"))
    )
    (net (code "12") (name "EPD_RST") (class "Default")
      (node (ref "J2") (pin "10") (pinfunction "10_10") (pintype "bidirectional"))
      (node (ref "U$1") (pin "P$AC11") (pinfunction "P0.16_P$AC11") (pintype "bidirectional"))
    )
    (net (code "13") (name "GDR") (class "Default")
      (node (ref "J2") (pin "2") (pinfunction "2_2") (pintype "bidirectional"))
      (node (ref "Q3") (pin "1") (pinfunction "G_1") (pintype "bidirectional"))
      (node (ref "R2_EP_DR") (pin "2") (pinfunction "2_2") (pintype "bidirectional"))
    )
    (net (code "14") (name "GND") (class "Default")
      (node (ref "C1") (pin "2") (pinfunction "2_2") (pintype "passive"))
      (node (ref "C1-EP-DR") (pin "2") (pinfunction "2_2") (pintype "passive"))
      (node (ref "C10") (pin "2") (pinfunction "2_2") (pintype "passive"))
      (node (ref "C11") (pin "2") (pinfunction "2_2") (pintype "passive"))
      (node (ref "C12") (pin "2") (pinfunction "2_2") (pintype "passive"))
      (node (ref "C13") (pin "2") (pinfunction "2_2") (pintype "passive"))
      (node (ref "C14") (pin "2") (pinfunction "2_2") (pintype "passive"))
      (node (ref "C15") (pin "2") (pinfunction "2_2") (pintype "passive"))
      (node (ref "C16") (pin "2") (pinfunction "2_2") (pintype "passive"))
      (node (ref "C17") (pin "1") (pinfunction "1_1") (pintype "passive"))
      (node (ref "C18") (pin "1") (pinfunction "1_1") (pintype "passive"))
      (node (ref "C19") (pin "2") (pinfunction "2_2") (pintype "passive"))
      (node (ref "C2") (pin "2") (pinfunction "2_2") (pintype "passive"))
      (node (ref "C20") (pin "2") (pinfunction "2_2") (pintype "passive"))
      (node (ref "C21") (pin "2") (pinfunction "2_2") (pintype "passive"))
      (node (ref "C22") (pin "2") (pinfunction "2_2") (pintype "passive"))
      (node (ref "C23") (pin "2") (pinfunction "2_2") (pintype "passive"))
      (node (ref "C24") (pin "1") (pinfunction "1_1") (pintype "passive"))
      (node (ref "C25") (pin "2") (pinfunction "2_2") (pintype "passive"))
      (node (ref "C27") (pin "1") (pinfunction "1_1") (pintype "passive"))
      (node (ref "C29") (pin "1") (pinfunction "1_1") (pintype "passive"))
      (node (ref "C3") (pin "2") (pinfunction "2_2") (pintype "passive"))
      (node (ref "C30") (pin "1") (pinfunction "1_1") (pintype "passive"))
      (node (ref "C31") (pin "1") (pinfunction "1_1") (pintype "passive"))
      (node (ref "C32") (pin "1") (pinfunction "1_1") (pintype "passive"))
      (node (ref "C33") (pin "2") (pinfunction "2_2") (pintype "passive"))
      (node (ref "C34") (pin "1") (pinfunction "1_1") (pintype "passive"))
      (node (ref "C37") (pin "1") (pinfunction "1_1") (pintype "passive"))
      (node (ref "C38") (pin "1") (pinfunction "1_1") (pintype "passive"))
      (node (ref "C39") (pin "2") (pinfunction "2_2") (pintype "passive"))
      (node (ref "C4") (pin "2") (pinfunction "2_2") (pintype "passive"))
      (node (ref "C42") (pin "2") (pinfunction "2_2") (pintype "passive"))
      (node (ref "C43") (pin "2") (pinfunction "2_2") (pintype "passive"))
      (node (ref "C5") (pin "2") (pinfunction "2_2") (pintype "passive"))
      (node (ref "C6") (pin "2") (pinfunction "2_2") (pintype "passive"))
      (node (ref "C7") (pin "2") (pinfunction "2_2") (pintype "passive"))
      (node (ref "C8") (pin "2") (pinfunction "2_2") (pintype "passive"))
      (node (ref "C9") (pin "2") (pinfunction "2_2") (pintype "passive"))
      (node (ref "D3") (pin "2") (pinfunction "GND_2") (pintype "bidirectional"))
      (node (ref "D4") (pin "1") (pinfunction "K_1") (pintype "bidirectional"))
      (node (ref "EPD_C1") (pin "1") (pinfunction "1_1") (pintype "passive"))
      (node (ref "EPD_C10") (pin "1") (pinfunction "1_1") (pintype "passive"))
      (node (ref "EPD_C11") (pin "1") (pinfunction "1_1") (pintype "passive"))
      (node (ref "EPD_C12") (pin "1") (pinfunction "1_1") (pintype "passive"))
      (node (ref "EPD_C2") (pin "1") (pinfunction "1_1") (pintype "passive"))
      (node (ref "EPD_C5") (pin "1") (pinfunction "1_1") (pintype "passive"))
      (node (ref "EPD_C6") (pin "1") (pinfunction "1_1") (pintype "passive"))
      (node (ref "EPD_C7") (pin "1") (pinfunction "1_1") (pintype "passive"))
      (node (ref "EPD_C8") (pin "1") (pinfunction "1_1") (pintype "passive"))
      (node (ref "EPD_C9") (pin "1") (pinfunction "1_1") (pintype "passive"))
      (node (ref "IC1") (pin "D2") (pinfunction "GND_D2") (pintype "bidirectional"))
      (node (ref "IC2") (pin "B1") (pinfunction "VSEL_B1") (pintype "bidirectional"))
      (node (ref "IC2") (pin "C1") (pinfunction "AGND_C1") (pintype "bidirectional"))
      (node (ref "IC2") (pin "C2") (pinfunction "PGND_1_C2") (pintype "bidirectional"))
      (node (ref "IC2") (pin "C3") (pinfunction "PGND_2_C3") (pintype "bidirectional"))
      (node (ref "IC3") (pin "8") (pinfunction "GNDIO_8") (pintype "bidirectional"))
      (node (ref "IC3") (pin "9") (pinfunction "GND_9") (pintype "bidirectional"))
      (node (ref "IC4") (pin "B1") (pinfunction "IN/TRIG_B1") (pintype "bidirectional"))
      (node (ref "IC4") (pin "B3") (pinfunction "GND_B3") (pintype "bidirectional"))
      (node (ref "J1") (pin "3") (pinfunction "3_3") (pintype "bidirectional"))
      (node (ref "J1") (pin "5") (pinfunction "5_5") (pintype "bidirectional"))
      (node (ref "J2") (pin "17") (pinfunction "17_17") (pintype "bidirectional"))
      (node (ref "J2") (pin "8") (pinfunction "8_8") (pintype "bidirectional"))
      (node (ref "J2") (pin "MP1") (pinfunction "MP1_MP1") (pintype "bidirectional"))
      (node (ref "J2") (pin "MP2") (pinfunction "MP2_MP2") (pintype "bidirectional"))
      (node (ref "J4") (pin "A12_B1") (pinfunction "GND_A12_B1") (pintype "power_in"))
      (node (ref "J4") (pin "A1_B12") (pinfunction "GND_A1_B12") (pintype "power_in"))
      (node (ref "J4") (pin "SH1") (pinfunction "SHIELD_SH1") (pintype "passive"))
      (node (ref "J4") (pin "SH2") (pinfunction "SHIELD_SH2") (pintype "passive"))
      (node (ref "J4") (pin "SH3") (pinfunction "SHIELD_SH3") (pintype "passive"))
      (node (ref "J4") (pin "SH4") (pinfunction "SHIELD_SH4") (pintype "passive"))
      (node (ref "R1_USB") (pin "1") (pinfunction "1_1") (pintype "bidirectional"))
      (node (ref "R2_EP_DR") (pin "1") (pinfunction "1_1") (pintype "bidirectional"))
      (node (ref "R2_USB") (pin "2") (pinfunction "2_2") (pintype "bidirectional"))
      (node (ref "R3") (pin "2") (pinfunction "2_2") (pintype "bidirectional"))
      (node (ref "R9") (pin "1") (pinfunction "1_1") (pintype "bidirectional"))
      (node (ref "R_TYPE_SEL") (pin "1") (pinfunction "1_1") (pintype "bidirectional"))
      (node (ref "SJ1") (pin "1") (pinfunction "1_1") (pintype "passive"))
      (node (ref "SW_DN") (pin "1") (pinfunction "1_1") (pintype "passive"))
      (node (ref "SW_ENT") (pin "1") (pinfunction "1_1") (pintype "passive"))
      (node (ref "SW_UP") (pin "1") (pinfunction "1_1") (pintype "passive"))
      (node (ref "TP_BAT_GND") (pin "TP") (pinfunction "TP_TP") (pintype "input"))
      (node (ref "TP_GND") (pin "TP") (pinfunction "TP_TP") (pintype "input"))
      (node (ref "U$1") (pin "P$74") (pinfunction "VSS_PAD_P$74") (pintype "bidirectional"))
      (node (ref "U$1") (pin "P$75") (pinfunction "VSS_PAD_P$75") (pintype "bidirectional"))
      (node (ref "U$1") (pin "P$76") (pinfunction "VSS_PAD_P$76") (pintype "bidirectional"))
      (node (ref "U$1") (pin "P$77") (pinfunction "VSS_PAD_P$77") (pintype "bidirectional"))
      (node (ref "U$1") (pin "P$78") (pinfunction "VSS_PAD_P$78") (pintype "bidirectional"))
      (node (ref "U$1") (pin "P$79") (pinfunction "VSS_PAD_P$79") (pintype "bidirectional"))
      (node (ref "U$1") (pin "P$80") (pinfunction "VSS_PAD_P$80") (pintype "bidirectional"))
      (node (ref "U$1") (pin "P$81") (pinfunction "VSS_PAD_P$81") (pintype "bidirectional"))
      (node (ref "U$1") (pin "P$82") (pinfunction "VSS_PAD_P$82") (pintype "bidirectional"))
      (node (ref "U$1") (pin "P$83") (pinfunction "VSS_PAD_P$83") (pintype "bidirectional"))
      (node (ref "U$1") (pin "P$84") (pinfunction "VSS_PAD_P$84") (pintype "bidirectional"))
      (node (ref "U$1") (pin "P$85") (pinfunction "VSS_PAD_P$85") (pintype "bidirectional"))
      (node (ref "U$1") (pin "P$86") (pinfunction "VSS_PAD_P$86") (pintype "bidirectional"))
      (node (ref "U$1") (pin "P$87") (pinfunction "VSS_PAD_P$87") (pintype "bidirectional"))
      (node (ref "U$1") (pin "P$88") (pinfunction "VSS_PAD_P$88") (pintype "bidirectional"))
      (node (ref "U$1") (pin "P$89") (pinfunction "VSS_PAD_P$89") (pintype "bidirectional"))
      (node (ref "U$1") (pin "P$90") (pinfunction "VSS_PAD_P$90") (pintype "bidirectional"))
      (node (ref "U$1") (pin "P$B7") (pinfunction "VSS_P$B7") (pintype "power_in"))
      (node (ref "U$1") (pin "P$F23") (pinfunction "VSS_PA_P$F23") (pintype "bidirectional"))
      (node (ref "U3") (pin "1") (pinfunction "CTG_1") (pintype "power_in"))
      (node (ref "U3") (pin "4") (pinfunction "GND_4") (pintype "power_in"))
      (node (ref "U3") (pin "6") (pinfunction "QSTRT_6") (pintype "input"))
      (node (ref "U3") (pin "9") (pinfunction "EP_9") (pintype "power_in"))
      (node (ref "X1") (pin "2") (pinfunction "2_2") (pintype "passive"))
      (node (ref "X1") (pin "4") (pinfunction "4_4") (pintype "passive"))
    )
    (net (code "15") (name "HAPTIC_EN") (class "Default")
      (node (ref "IC4") (pin "A1") (pinfunction "EN_A1") (pintype "bidirectional"))
      (node (ref "U$1") (pin "P$U1") (pinfunction "P0.12_P$U1") (pintype "bidirectional"))
    )
    (net (code "16") (name "IMU_INT1") (class "Default")
      (node (ref "IC3") (pin "5") (pinfunction "INT1_5") (pintype "bidirectional"))
      (node (ref "U$1") (pin "P$N1") (pinfunction "P0.08_P$N1") (pintype "bidirectional"))
    )
    (net (code "17") (name "IMU_INT2") (class "Default")
      (node (ref "IC3") (pin "6") (pinfunction "INT2_6") (pintype "bidirectional"))
      (node (ref "U$1") (pin "P$P2") (pinfunction "P1.08_P$P2") (pintype "bidirectional"))
    )
    (net (code "18") (name "LX1") (class "Default")
      (node (ref "IC2") (pin "B2") (pinfunction "SW1_1_B2") (pintype "bidirectional"))
      (node (ref "IC2") (pin "B3") (pinfunction "SW1_2_B3") (pintype "bidirectional"))
      (node (ref "L7") (pin "1") (pinfunction "1_1") (pintype "bidirectional"))
    )
    (net (code "19") (name "LX2") (class "Default")
      (node (ref "IC2") (pin "D2") (pinfunction "SW2_1_D2") (pintype "bidirectional"))
      (node (ref "IC2") (pin "D3") (pinfunction "SW2_2_D3") (pintype "bidirectional"))
      (node (ref "L7") (pin "2") (pinfunction "2_2") (pintype "bidirectional"))
    )
    (net (code "20") (name "MOSI") (class "Default")
      (node (ref "J2") (pin "14") (pinfunction "14_14") (pintype "bidirectional"))
      (node (ref "U$1") (pin "P$B13") (pinfunction "P0.03/AIN1_P$B13") (pintype "bidirectional"))
    )
    (net (code "21") (name "Net-(ANT1-FEED)") (class "Default")
      (node (ref "ANT1") (pin "1") (pinfunction "FEED_1") (pintype "input"))
      (node (ref "C22") (pin "1") (pinfunction "1_1") (pintype "passive"))
      (node (ref "C4") (pin "1") (pinfunction "1_1") (pintype "passive"))
      (node (ref "L1") (pin "2") (pinfunction "2_2") (pintype "passive"))
    )
    (net (code "22") (name "Net-(D2-K)") (class "Default")
      (node (ref "C2-EP-DR") (pin "1") (pinfunction "1_1") (pintype "passive"))
      (node (ref "D2") (pin "1") (pinfunction "K_1") (pintype "bidirectional"))
      (node (ref "D4") (pin "2") (pinfunction "A_2") (pintype "bidirectional"))
    )
    (net (code "23") (name "Net-(D5-A)") (class "Default")
      (node (ref "C2-EP-DR") (pin "2") (pinfunction "2_2") (pintype "passive"))
      (node (ref "D5") (pin "2") (pinfunction "A_2") (pintype "bidirectional"))
      (node (ref "L5") (pin "1") (pinfunction "1_1") (pintype "passive"))
      (node (ref "Q3") (pin "3") (pinfunction "D_3") (pintype "bidirectional"))
    )
    (net (code "24") (name "Net-(EPD_C1-Pad2)") (class "Default")
      (node (ref "EPD_C1") (pin "2") (pinfunction "2_2") (pintype "passive"))
      (node (ref "J2") (pin "5") (pinfunction "5_5") (pintype "bidirectional"))
    )
    (net (code "25") (name "Net-(EPD_C2-Pad2)") (class "Default")
      (node (ref "EPD_C2") (pin "2") (pinfunction "2_2") (pintype "passive"))
      (node (ref "J2") (pin "4") (pinfunction "4_4") (pintype "bidirectional"))
    )
    (net (code "26") (name "Net-(EPD_C6-Pad2)") (class "Default")
      (node (ref "EPD_C6") (pin "2") (pinfunction "2_2") (pintype "passive"))
      (node (ref "J2") (pin "18") (pinfunction "18_18") (pintype "bidirectional"))
    )
    (net (code "27") (name "Net-(EPD_C7-Pad2)") (class "Default")
      (node (ref "EPD_C7") (pin "2") (pinfunction "2_2") (pintype "passive"))
      (node (ref "J2") (pin "19") (pinfunction "19_19") (pintype "bidirectional"))
    )
    (net (code "28") (name "Net-(EPD_C8-Pad2)") (class "Default")
      (node (ref "EPD_C8") (pin "2") (pinfunction "2_2") (pintype "passive"))
      (node (ref "J2") (pin "20") (pinfunction "20_20") (pintype "bidirectional"))
    )
    (net (code "29") (name "Net-(EPD_C10-Pad2)") (class "Default")
      (node (ref "EPD_C10") (pin "2") (pinfunction "2_2") (pintype "passive"))
      (node (ref "J2") (pin "22") (pinfunction "22_22") (pintype "bidirectional"))
    )
    (net (code "30") (name "Net-(EPD_C12-Pad2)") (class "Default")
      (node (ref "EPD_C12") (pin "2") (pinfunction "2_2") (pintype "passive"))
      (node (ref "J2") (pin "24") (pinfunction "24_24") (pintype "bidirectional"))
    )
    (net (code "31") (name "Net-(IC1-TS{slash}MR)") (class "Default")
      (node (ref "IC1") (pin "D1") (pinfunction "TS/MR_D1") (pintype "bidirectional"))
      (node (ref "R9") (pin "2") (pinfunction "2_2") (pintype "bidirectional"))
    )
    (net (code "32") (name "Net-(IC2-SCL)") (class "Default")
      (node (ref "IC2") (pin "D1") (pinfunction "SCL_D1") (pintype "bidirectional"))
      (node (ref "R4") (pin "2") (pinfunction "2_2") (pintype "bidirectional"))
    )
    (net (code "33") (name "Net-(IC2-SDA)") (class "Default")
      (node (ref "IC2") (pin "E1") (pinfunction "SDA_E1") (pintype "bidirectional"))
      (node (ref "R2") (pin "2") (pinfunction "2_2") (pintype "bidirectional"))
    )
    (net (code "34") (name "Net-(IC3-SDO)") (class "Default")
      (node (ref "IC3") (pin "1") (pinfunction "SDO_1") (pintype "bidirectional"))
      (node (ref "R3") (pin "1") (pinfunction "1_1") (pintype "bidirectional"))
    )
    (net (code "35") (name "Net-(IC4-REG)") (class "Default")
      (node (ref "C32") (pin "2") (pinfunction "2_2") (pintype "passive"))
      (node (ref "IC4") (pin "A2") (pinfunction "REG_A2") (pintype "bidirectional"))
    )
    (net (code "36") (name "Net-(J4-CC1)") (class "Default")
      (node (ref "J4") (pin "A5") (pinfunction "CC1_A5") (pintype "bidirectional"))
      (node (ref "R1_USB") (pin "2") (pinfunction "2_2") (pintype "bidirectional"))
    )
    (net (code "37") (name "Net-(J4-CC2)") (class "Default")
      (node (ref "J4") (pin "B5") (pinfunction "CC2_B5") (pintype "bidirectional"))
      (node (ref "R2_USB") (pin "1") (pinfunction "1_1") (pintype "bidirectional"))
    )
    (net (code "38") (name "Net-(L2-Pad2)") (class "Default")
      (node (ref "L2") (pin "2") (pinfunction "2_2") (pintype "passive"))
      (node (ref "L3") (pin "1") (pinfunction "1_1") (pintype "passive"))
    )
    (net (code "39") (name "Net-(R1_EP_DR-Pad1)") (class "Default")
      (node (ref "R1_EP_DR") (pin "1") (pinfunction "1_1") (pintype "bidirectional"))
      (node (ref "R_TYPE_SEL") (pin "2") (pinfunction "2_2") (pintype "bidirectional"))
      (node (ref "SJ1") (pin "2") (pinfunction "2_2") (pintype "passive"))
    )
    (net (code "40") (name "Net-(U$1-ANT)") (class "Default")
      (node (ref "C3") (pin "1") (pinfunction "1_1") (pintype "passive"))
      (node (ref "L1") (pin "1") (pinfunction "1_1") (pintype "passive"))
      (node (ref "U$1") (pin "P$H23") (pinfunction "ANT_P$H23") (pintype "bidirectional"))
    )
    (net (code "41") (name "Net-(U$1-DCC)") (class "Default")
      (node (ref "L2") (pin "1") (pinfunction "1_1") (pintype "passive"))
      (node (ref "U$1") (pin "P$B3") (pinfunction "DCC_P$B3") (pintype "output"))
    )
    (net (code "42") (name "Net-(U$1-DEC1)") (class "Default")
      (node (ref "C5") (pin "1") (pinfunction "1_1") (pintype "passive"))
      (node (ref "U$1") (pin "P$C1") (pinfunction "DEC1_P$C1") (pintype "power_in"))
    )
    (net (code "43") (name "Net-(U$1-DEC2)") (class "Default")
      (node (ref "C13") (pin "1") (pinfunction "1_1") (pintype "passive"))
      (node (ref "U$1") (pin "P$A18") (pinfunction "DEC2_P$A18") (pintype "bidirectional"))
    )
    (net (code "44") (name "Net-(U$1-DEC3)") (class "Default")
      (node (ref "C11") (pin "1") (pinfunction "1_1") (pintype "passive"))
      (node (ref "U$1") (pin "P$D23") (pinfunction "DEC3_P$D23") (pintype "bidirectional"))
    )
    (net (code "45") (name "Net-(U$1-DEC3V3)") (class "Default")
      (node (ref "C20") (pin "1") (pinfunction "1_1") (pintype "passive"))
      (node (ref "U$1") (pin "P$AC5") (pinfunction "DEC3V3_P$AC5") (pintype "bidirectional"))
    )
    (net (code "46") (name "Net-(U$1-DEC4)") (class "Default")
      (node (ref "C10") (pin "1") (pinfunction "1_1") (pintype "passive"))
      (node (ref "C15") (pin "1") (pinfunction "1_1") (pintype "passive"))
      (node (ref "C16") (pin "1") (pinfunction "1_1") (pintype "passive"))
      (node (ref "L3") (pin "2") (pinfunction "2_2") (pintype "passive"))
      (node (ref "U$1") (pin "P$B5") (pinfunction "DEC4_P$B5") (pintype "power_in"))
      (node (ref "U$1") (pin "P$E24") (pinfunction "DEC6_P$E24") (pintype "bidirectional"))
    )
    (net (code "47") (name "Net-(U$1-DEC5)") (class "Default")
      (node (ref "C9") (pin "1") (pinfunction "1_1") (pintype "passive"))
      (node (ref "U$1") (pin "P$N24") (pinfunction "DEC5_P$N24") (pintype "bidirectional"))
    )
    (net (code "48") (name "Net-(U$1-P0.00{slash}XL1)") (class "Default")
      (node (ref "C17") (pin "2") (pinfunction "2_2") (pintype "passive"))
      (node (ref "U$1") (pin "P$D2") (pinfunction "P0.00/XL1_P$D2") (pintype "bidirectional"))
      (node (ref "X2") (pin "2") (pinfunction "2_2") (pintype "passive"))
    )
    (net (code "49") (name "Net-(U$1-P0.01{slash}XL2)") (class "Default")
      (node (ref "C18") (pin "2") (pinfunction "2_2") (pintype "passive"))
      (node (ref "U$1") (pin "P$F2") (pinfunction "P0.01/XL2_P$F2") (pintype "bidirectional"))
      (node (ref "X2") (pin "1") (pinfunction "1_1") (pintype "passive"))
    )
    (net (code "50") (name "Net-(U$1-XC1)") (class "Default")
      (node (ref "C1") (pin "1") (pinfunction "1_1") (pintype "passive"))
      (node (ref "U$1") (pin "P$B24") (pinfunction "XC1_P$B24") (pintype "input"))
      (node (ref "X1") (pin "1") (pinfunction "1_1") (pintype "passive"))
    )
    (net (code "51") (name "Net-(U$1-XC2)") (class "Default")
      (node (ref "C2") (pin "1") (pinfunction "1_1") (pintype "passive"))
      (node (ref "U$1") (pin "P$A23") (pinfunction "XC2_P$A23") (pintype "output"))
      (node (ref "X1") (pin "3") (pinfunction "3_3") (pintype "passive"))
    )
    (net (code "52") (name "OUT+") (class "Default")
      (node (ref "IC4") (pin "A3") (pinfunction "OUT+_A3") (pintype "bidirectional"))
      (node (ref "TP1") (pin "TP") (pinfunction "TP_TP") (pintype "input"))
    )
    (net (code "53") (name "OUT-") (class "Default")
      (node (ref "IC4") (pin "C3") (pinfunction "OUT-_C3") (pintype "bidirectional"))
      (node (ref "TP2") (pin "TP") (pinfunction "TP_TP") (pintype "input"))
    )
    (net (code "54") (name "P0.04") (class "Default")
      (node (ref "U$1") (pin "P$J1") (pinfunction "P0.04/AIN2_P$J1") (pintype "bidirectional"))
    )
    (net (code "55") (name "P0.09") (class "Default")
      (node (ref "U$1") (pin "P$L24") (pinfunction "P0.09/NFC1_P$L24") (pintype "bidirectional"))
    )
    (net (code "56") (name "P0.13") (class "Default")
      (node (ref "C30") (pin "2") (pinfunction "2_2") (pintype "passive"))
      (node (ref "R1") (pin "1") (pinfunction "1_1") (pintype "bidirectional"))
      (node (ref "SW_UP") (pin "2") (pinfunction "2_2") (pintype "passive"))
      (node (ref "U$1") (pin "P$AD8") (pinfunction "P0.13_P$AD8") (pintype "bidirectional"))
    )
    (net (code "57") (name "P0.14") (class "Default")
      (node (ref "C31") (pin "2") (pinfunction "2_2") (pintype "passive"))
      (node (ref "R5") (pin "1") (pinfunction "1_1") (pintype "bidirectional"))
      (node (ref "SW_ENT") (pin "2") (pinfunction "2_2") (pintype "passive"))
      (node (ref "U$1") (pin "P$AC9") (pinfunction "P0.14_P$AC9") (pintype "bidirectional"))
    )
    (net (code "58") (name "P0.19") (class "Default")
      (node (ref "U$1") (pin "P$AC15") (pinfunction "P0.19_P$AC15") (pintype "bidirectional"))
    )
    (net (code "59") (name "P0.20") (class "Default")
      (node (ref "U$1") (pin "P$AD16") (pinfunction "P0.20_P$AD16") (pintype "bidirectional"))
    )
    (net (code "60") (name "P0.21") (class "Default")
      (node (ref "U$1") (pin "P$AC17") (pinfunction "P0.21_P$AC17") (pintype "bidirectional"))
    )
    (net (code "61") (name "P0.22") (class "Default")
      (node (ref "U$1") (pin "P$AD18") (pinfunction "P0.22_P$AD18") (pintype "bidirectional"))
    )
    (net (code "62") (name "P0.23") (class "Default")
      (node (ref "U$1") (pin "P$AC19") (pinfunction "P0.23_P$AC19") (pintype "bidirectional"))
    )
    (net (code "63") (name "P0.24") (class "Default")
      (node (ref "U$1") (pin "P$AD20") (pinfunction "P0.24_P$AD20") (pintype "bidirectional"))
    )
    (net (code "64") (name "P0.25") (class "Default")
      (node (ref "U$1") (pin "P$AC21") (pinfunction "P0.25_P$AC21") (pintype "bidirectional"))
    )
    (net (code "65") (name "P0.26") (class "Default")
      (node (ref "U$1") (pin "P$G1") (pinfunction "P0.26_P$G1") (pintype "bidirectional"))
    )
    (net (code "66") (name "P0.27") (class "Default")
      (node (ref "U$1") (pin "P$H2") (pinfunction "P0.27_P$H2") (pintype "bidirectional"))
    )
    (net (code "67") (name "P0.28") (class "Default")
      (node (ref "U$1") (pin "P$B11") (pinfunction "P0.28/AIN4_P$B11") (pintype "bidirectional"))
    )
    (net (code "68") (name "P0.29") (class "Default")
      (node (ref "U$1") (pin "P$A10") (pinfunction "P0.29/AIN5_P$A10") (pintype "bidirectional"))
    )
    (net (code "69") (name "P0.30") (class "Default")
      (node (ref "U$1") (pin "P$B9") (pinfunction "P0.30/AIN6_P$B9") (pintype "bidirectional"))
    )
    (net (code "70") (name "P0.31") (class "Default")
      (node (ref "U$1") (pin "P$A8") (pinfunction "P0.31/AIN7_P$A8") (pintype "bidirectional"))
    )
    (net (code "71") (name "P1.01") (class "Default")
      (node (ref "Q1") (pin "1") (pinfunction "G_1") (pintype "bidirectional"))
      (node (ref "R_PWR_EPD") (pin "1") (pinfunction "1_1") (pintype "bidirectional"))
      (node (ref "U$1") (pin "P$Y23") (pinfunction "P1.01_P$Y23") (pintype "bidirectional"))
    )
    (net (code "72") (name "P1.02") (class "Default")
      (node (ref "C29") (pin "2") (pinfunction "2_2") (pintype "passive"))
      (node (ref "R6") (pin "1") (pinfunction "1_1") (pintype "bidirectional"))
      (node (ref "SW_DN") (pin "2") (pinfunction "2_2") (pintype "passive"))
      (node (ref "U$1") (pin "P$W24") (pinfunction "P1.02_P$W24") (pintype "bidirectional"))
    )
    (net (code "73") (name "P1.03") (class "Default")
      (node (ref "U$1") (pin "P$V23") (pinfunction "P1.03_P$V23") (pintype "bidirectional"))
    )
    (net (code "74") (name "P1.04") (class "Default")
      (node (ref "U$1") (pin "P$U24") (pinfunction "P1.04_P$U24") (pintype "bidirectional"))
    )
    (net (code "75") (name "P1.05") (class "Default")
      (node (ref "U$1") (pin "P$T23") (pinfunction "P1.05_P$T23") (pintype "bidirectional"))
    )
    (net (code "76") (name "P1.06") (class "Default")
      (node (ref "U$1") (pin "P$R24") (pinfunction "P1.06_P$R24") (pintype "bidirectional"))
    )
    (net (code "77") (name "P1.07") (class "Default")
      (node (ref "U$1") (pin "P$P23") (pinfunction "P1.07_P$P23") (pintype "bidirectional"))
    )
    (net (code "78") (name "P1.09") (class "Default")
      (node (ref "U$1") (pin "P$R1") (pinfunction "P1.09_P$R1") (pintype "bidirectional"))
    )
    (net (code "79") (name "P1.10") (class "Default")
      (node (ref "U$1") (pin "P$A20") (pinfunction "P1.10_P$A20") (pintype "bidirectional"))
    )
    (net (code "80") (name "P1.11") (class "Default")
      (node (ref "U$1") (pin "P$B19") (pinfunction "P1.11_P$B19") (pintype "bidirectional"))
    )
    (net (code "81") (name "P1.12") (class "Default")
      (node (ref "U$1") (pin "P$B17") (pinfunction "P1.12_P$B17") (pintype "bidirectional"))
    )
    (net (code "82") (name "P1.13") (class "Default")
      (node (ref "U$1") (pin "P$A16") (pinfunction "P1.13_P$A16") (pintype "bidirectional"))
    )
    (net (code "83") (name "P1.14") (class "Default")
      (node (ref "U$1") (pin "P$B15") (pinfunction "P1.14_P$B15") (pintype "bidirectional"))
    )
    (net (code "84") (name "P1.15") (class "Default")
      (node (ref "U$1") (pin "P$A14") (pinfunction "P1.15_P$A14") (pintype "bidirectional"))
    )
    (net (code "85") (name "PMIC_INT") (class "Default")
      (node (ref "IC1") (pin "A1") (pinfunction "~{INT}_A1") (pintype "bidirectional"))
      (node (ref "U$1") (pin "P$T2") (pinfunction "P0.11_P$T2") (pintype "bidirectional"))
    )
    (net (code "86") (name "PREVGH") (class "Default")
      (node (ref "D5") (pin "1") (pinfunction "K_1") (pintype "bidirectional"))
      (node (ref "EPD_C9") (pin "2") (pinfunction "2_2") (pintype "passive"))
      (node (ref "J2") (pin "21") (pinfunction "21_21") (pintype "bidirectional"))
    )
    (net (code "87") (name "PREVGL") (class "Default")
      (node (ref "D2") (pin "2") (pinfunction "A_2") (pintype "bidirectional"))
      (node (ref "EPD_C11") (pin "2") (pinfunction "2_2") (pintype "passive"))
      (node (ref "J2") (pin "23") (pinfunction "23_23") (pintype "bidirectional"))
    )
    (net (code "88") (name "RESE") (class "Default")
      (node (ref "J2") (pin "3") (pinfunction "3_3") (pintype "bidirectional"))
      (node (ref "Q3") (pin "2") (pinfunction "S_2") (pintype "bidirectional"))
      (node (ref "R1_EP_DR") (pin "2") (pinfunction "2_2") (pintype "bidirectional"))
    )
    (net (code "89") (name "RESET") (class "Default")
      (node (ref "J1") (pin "6") (pinfunction "6_6") (pintype "bidirectional"))
      (node (ref "TP_RESET") (pin "TP") (pinfunction "TP_TP") (pintype "input"))
      (node (ref "U$1") (pin "P$AC13") (pinfunction "P0.18/RESET_P$AC13") (pintype "bidirectional"))
    )
    (net (code "90") (name "SCK") (class "Default")
      (node (ref "J2") (pin "13") (pinfunction "13_13") (pintype "bidirectional"))
      (node (ref "U$1") (pin "P$A12") (pinfunction "P0.02/AIN0_P$A12") (pintype "bidirectional"))
    )
    (net (code "91") (name "SCL") (class "Default")
      (node (ref "IC1") (pin "B1") (pinfunction "SCL_B1") (pintype "bidirectional"))
      (node (ref "IC3") (pin "12") (pinfunction "SCX_12") (pintype "bidirectional"))
      (node (ref "IC4") (pin "C1") (pinfunction "SCL_C1") (pintype "bidirectional"))
      (node (ref "R17") (pin "2") (pinfunction "2_2") (pintype "bidirectional"))
      (node (ref "R4") (pin "1") (pinfunction "1_1") (pintype "bidirectional"))
      (node (ref "TP_SCL") (pin "TP") (pinfunction "TP_TP") (pintype "input"))
      (node (ref "U$1") (pin "P$M2") (pinfunction "P0.07_P$M2") (pintype "bidirectional"))
      (node (ref "U3") (pin "7") (pinfunction "SCL_7") (pintype "input"))
    )
    (net (code "92") (name "SDA") (class "Default")
      (node (ref "IC1") (pin "C1") (pinfunction "SDA_C1") (pintype "bidirectional"))
      (node (ref "IC3") (pin "2") (pinfunction "SDX_2") (pintype "bidirectional"))
      (node (ref "IC4") (pin "B2") (pinfunction "SDA_B2") (pintype "bidirectional"))
      (node (ref "R18") (pin "2") (pinfunction "2_2") (pintype "bidirectional"))
      (node (ref "R2") (pin "1") (pinfunction "1_1") (pintype "bidirectional"))
      (node (ref "TP_SDA") (pin "TP") (pinfunction "TP_TP") (pintype "input"))
      (node (ref "U$1") (pin "P$L1") (pinfunction "P0.06_P$L1") (pintype "bidirectional"))
      (node (ref "U3") (pin "8") (pinfunction "SDA_8") (pintype "bidirectional"))
    )
    (net (code "93") (name "SWDCLK") (class "Default")
      (node (ref "J1") (pin "4") (pinfunction "4_4") (pintype "bidirectional"))
      (node (ref "TP_SWDCLK") (pin "TP") (pinfunction "TP_TP") (pintype "input"))
      (node (ref "U$1") (pin "P$AA24") (pinfunction "SWDCLK_P$AA24") (pintype "input"))
    )
    (net (code "94") (name "SWDIO") (class "Default")
      (node (ref "J1") (pin "2") (pinfunction "2_2") (pintype "bidirectional"))
      (node (ref "TP_SWDIO") (pin "TP") (pinfunction "TP_TP") (pintype "input"))
      (node (ref "U$1") (pin "P$AC24") (pinfunction "SWDIO_P$AC24") (pintype "bidirectional"))
    )
    (net (code "95") (name "SWO") (class "Default")
      (node (ref "TP_SWO") (pin "TP") (pinfunction "TP_TP") (pintype "input"))
      (node (ref "U$1") (pin "P$AD22") (pinfunction "P1.00_P$AD22") (pintype "bidirectional"))
    )
    (net (code "96") (name "VBAT") (class "Default")
      (node (ref "C27") (pin "2") (pinfunction "2_2") (pintype "passive"))
      (node (ref "C37") (pin "2") (pinfunction "2_2") (pintype "passive"))
      (node (ref "IC1") (pin "C2") (pinfunction "BAT_C2") (pintype "bidirectional"))
      (node (ref "TP_VBAT") (pin "TP") (pinfunction "TP_TP") (pintype "input"))
      (node (ref "U3") (pin "2") (pinfunction "CELL_2") (pintype "power_in"))
      (node (ref "U3") (pin "3") (pinfunction "VDD_3") (pintype "power_in"))
    )
    (net (code "97") (name "VBUS") (class "Default")
      (node (ref "C21") (pin "1") (pinfunction "1_1") (pintype "passive"))
      (node (ref "C38") (pin "2") (pinfunction "2_2") (pintype "passive"))
      (node (ref "C42") (pin "1") (pinfunction "1_1") (pintype "passive"))
      (node (ref "C43") (pin "1") (pinfunction "1_1") (pintype "passive"))
      (node (ref "D3") (pin "5") (pinfunction "VBUS_5") (pintype "bidirectional"))
      (node (ref "IC1") (pin "A2") (pinfunction "IN_A2") (pintype "bidirectional"))
      (node (ref "J4") (pin "A4_B9") (pinfunction "VBUS_A4_B9") (pintype "power_in"))
      (node (ref "J4") (pin "A9_B4") (pinfunction "VBUS_A9_B4") (pintype "power_in"))
      (node (ref "U$1") (pin "P$AD2") (pinfunction "VBUS_P$AD2") (pintype "power_in"))
    )
    (net (code "98") (name "VREG") (class "Default")
      (node (ref "C23") (pin "1") (pinfunction "1_1") (pintype "passive"))
      (node (ref "C24") (pin "2") (pinfunction "2_2") (pintype "passive"))
      (node (ref "C39") (pin "1") (pinfunction "1_1") (pintype "passive"))
      (node (ref "IC1") (pin "B2") (pinfunction "SYS_B2") (pintype "bidirectional"))
      (node (ref "IC2") (pin "A1") (pinfunction "EN_A1") (pintype "bidirectional"))
      (node (ref "IC2") (pin "A2") (pinfunction "VIN_1_A2") (pintype "bidirectional"))
      (node (ref "IC2") (pin "A3") (pinfunction "VIN_2_A3") (pintype "bidirectional"))
      (node (ref "TP_VREG") (pin "TP") (pinfunction "TP_TP") (pintype "input"))
    )
    (net (code "99") (name "unconnected-(ANT1-NC-Pad2)") (class "Default")
      (node (ref "ANT1") (pin "2") (pinfunction "NC_2") (pintype "no_connect"))
    )
    (net (code "100") (name "unconnected-(IC3-ASCL-Pad11)") (class "Default")
      (node (ref "IC3") (pin "11") (pinfunction "ASCL_11") (pintype "bidirectional"))
    )
    (net (code "101") (name "unconnected-(IC3-ASDA-Pad4)") (class "Default")
      (node (ref "IC3") (pin "4") (pinfunction "ASDA_4") (pintype "bidirectional"))
    )
    (net (code "102") (name "unconnected-(J2-Pad1)") (class "Default")
      (node (ref "J2") (pin "1") (pinfunction "1_1") (pintype "bidirectional"))
    )
    (net (code "103") (name "unconnected-(J2-Pad6)") (class "Default")
      (node (ref "J2") (pin "6") (pinfunction "6_6") (pintype "bidirectional"))
    )
    (net (code "104") (name "unconnected-(J2-Pad7)") (class "Default")
      (node (ref "J2") (pin "7") (pinfunction "7_7") (pintype "bidirectional"))
    )
    (net (code "105") (name "unconnected-(J4-SBU1-PadA8)") (class "Default")
      (node (ref "J4") (pin "A8") (pinfunction "SBU1_A8") (pintype "bidirectional"))
    )
    (net (code "106") (name "unconnected-(J4-SBU2-PadB8)") (class "Default")
      (node (ref "J4") (pin "B8") (pinfunction "SBU2_B8") (pintype "bidirectional"))
    )
    (net (code "107") (name "unconnected-(U$1-DCCH-PadP$AB2)") (class "Default")
      (node (ref "U$1") (pin "P$AB2") (pinfunction "DCCH_P$AB2") (pintype "bidirectional"))
    )
  )
)
